# FPGA_Bypass_1V2.net
KiCad netlist of a schematic drawn in Altium Designer
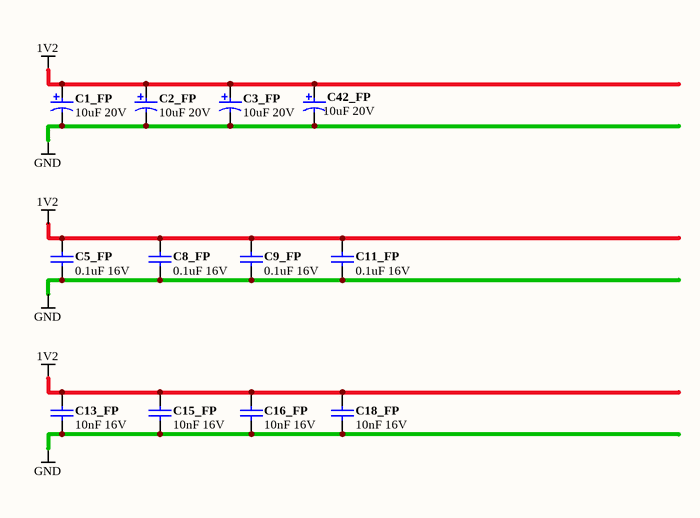
[diagram p0: FPGA_Bypass_1V2.SCHDOC]

(export (version "E")
  (design (tool "Eeschema 10.0.6"))
  (components
    (comp (ref "C1_FP")
      (value "10uF 20V")
      (footprint "CAPC3528-STAR")
      (description "Capacitor, Tantalum, 10uF 10% 20V MCCT-B (3528)")
      (fields (field (name "TOLERANCE") "10 %"))
      (libsource (lib "altium-import") (part "root_0_CAP-P_"))
    )
    (comp (ref "C2_FP")
      (value "10uF 20V")
      (footprint "CAPC3528-STAR")
      (description "Capacitor, Tantalum, 10uF 10% 20V MCCT-B (3528)")
      (fields (field (name "TOLERANCE") "10 %"))
      (libsource (lib "altium-import") (part "root_0_CAP-P_"))
    )
    (comp (ref "C3_FP")
      (value "10uF 20V")
      (footprint "CAPC3528-STAR")
      (description "Capacitor, Tantalum, 10uF 10% 20V MCCT-B (3528)")
      (fields (field (name "TOLERANCE") "10 %"))
      (libsource (lib "altium-import") (part "root_0_CAP-P_"))
    )
    (comp (ref "C5_FP")
      (value "0.1uF 16V")
      (footprint "CAPC1005-STAR")
      (description "Capacitor, Ceramic, 0.1uF 10% 16V 0402 (1005) X7R")
      (fields (field (name "TOLERANCE") "10 %"))
      (libsource (lib "altium-import") (part "root_0_mirrored_CAP-NP_"))
    )
    (comp (ref "C8_FP")
      (value "0.1uF 16V")
      (footprint "CAPC1005-STAR")
      (description "Capacitor, Ceramic, 0.1uF 10% 16V 0402 (1005) X7R")
      (fields (field (name "TOLERANCE") "10 %"))
      (libsource (lib "altium-import") (part "root_0_mirrored_CAP-NP_"))
    )
    (comp (ref "C9_FP")
      (value "0.1uF 16V")
      (footprint "CAPC1005-STAR")
      (description "Capacitor, Ceramic, 0.1uF 10% 16V 0402 (1005) X7R")
      (fields (field (name "TOLERANCE") "10 %"))
      (libsource (lib "altium-import") (part "root_0_mirrored_CAP-NP_"))
    )
    (comp (ref "C11_FP")
      (value "0.1uF 16V")
      (footprint "CAPC1005-STAR")
      (description "Capacitor, Ceramic, 0.1uF 10% 16V 0402 (1005) X7R")
      (fields (field (name "TOLERANCE") "10 %"))
      (libsource (lib "altium-import") (part "root_0_mirrored_CAP-NP_"))
    )
    (comp (ref "C13_FP")
      (value "10nF 16V")
      (footprint "CAPC1005-STAR")
      (description "Capacitor, Ceramic, 10nF 10% 16V 0402 (1005) X7R")
      (fields (field (name "TOLERANCE") "10 %"))
      (libsource (lib "altium-import") (part "root_0_CAP-NP_"))
    )
    (comp (ref "C15_FP")
      (value "10nF 16V")
      (footprint "CAPC1005-STAR")
      (description "Capacitor, Ceramic, 10nF 10% 16V 0402 (1005) X7R")
      (fields (field (name "TOLERANCE") "10 %"))
      (libsource (lib "altium-import") (part "root_0_CAP-NP_"))
    )
    (comp (ref "C16_FP")
      (value "10nF 16V")
      (footprint "CAPC1005-STAR")
      (description "Capacitor, Ceramic, 10nF 10% 16V 0402 (1005) X7R")
      (fields (field (name "TOLERANCE") "10 %"))
      (libsource (lib "altium-import") (part "root_0_CAP-NP_"))
    )
    (comp (ref "C18_FP")
      (value "10nF 16V")
      (footprint "CAPC1005-STAR")
      (description "Capacitor, Ceramic, 10nF 10% 16V 0402 (1005) X7R")
      (fields (field (name "TOLERANCE") "10 %"))
      (libsource (lib "altium-import") (part "root_0_CAP-NP_"))
    )
    (comp (ref "C42_FP")
      (value "10uF 20V")
      (footprint "CAPC3528-STAR")
      (description "Capacitor, Tantalum, 10uF 10% 20V MCCT-B (3528)")
      (fields (field (name "TOLERANCE") "10 %"))
      (libsource (lib "altium-import") (part "root_0_CAP-P_"))
    )
  )
  (nets
    (net (code "1") (name "1V2") (class "Default")
      (node (ref "C11_FP") (pin "1") (pinfunction "1_1") (pintype "passive"))
      (node (ref "C13_FP") (pin "1") (pinfunction "1_1") (pintype "passive"))
      (node (ref "C15_FP") (pin "1") (pinfunction "1_1") (pintype "passive"))
      (node (ref "C16_FP") (pin "1") (pinfunction "1_1") (pintype "passive"))
      (node (ref "C18_FP") (pin "1") (pinfunction "1_1") (pintype "passive"))
      (node (ref "C1_FP") (pin "1") (pinfunction "1_1") (pintype "passive"))
      (node (ref "C2_FP") (pin "1") (pinfunction "1_1") (pintype "passive"))
      (node (ref "C3_FP") (pin "1") (pinfunction "1_1") (pintype "passive"))
      (node (ref "C42_FP") (pin "1") (pinfunction "1_1") (pintype "passive"))
      (node (ref "C5_FP") (pin "1") (pinfunction "1_1") (pintype "passive"))
      (node (ref "C8_FP") (pin "1") (pinfunction "1_1") (pintype "passive"))
      (node (ref "C9_FP") (pin "1") (pinfunction "1_1") (pintype "passive"))
    )
    (net (code "2") (name "GND") (class "Default")
      (node (ref "C11_FP") (pin "2") (pinfunction "2_2") (pintype "passive"))
      (node (ref "C13_FP") (pin "2") (pinfunction "2_2") (pintype "passive"))
      (node (ref "C15_FP") (pin "2") (pinfunction "2_2") (pintype "passive"))
      (node (ref "C16_FP") (pin "2") (pinfunction "2_2") (pintype "passive"))
      (node (ref "C18_FP") (pin "2") (pinfunction "2_2") (pintype "passive"))
      (node (ref "C1_FP") (pin "2") (pinfunction "2_2") (pintype "passive"))
      (node (ref "C2_FP") (pin "2") (pinfunction "2_2") (pintype "passive"))
      (node (ref "C3_FP") (pin "2") (pinfunction "2_2") (pintype "passive"))
      (node (ref "C42_FP") (pin "2") (pinfunction "2_2") (pintype "passive"))
      (node (ref "C5_FP") (pin "2") (pinfunction "2_2") (pintype "passive"))
      (node (ref "C8_FP") (pin "2") (pinfunction "2_2") (pintype "passive"))
      (node (ref "C9_FP") (pin "2") (pinfunction "2_2") (pintype "passive"))
    )
  )
)
